# SCH___2023-03-02.net
KiCad netlist of a schematic drawn in EasyEDA
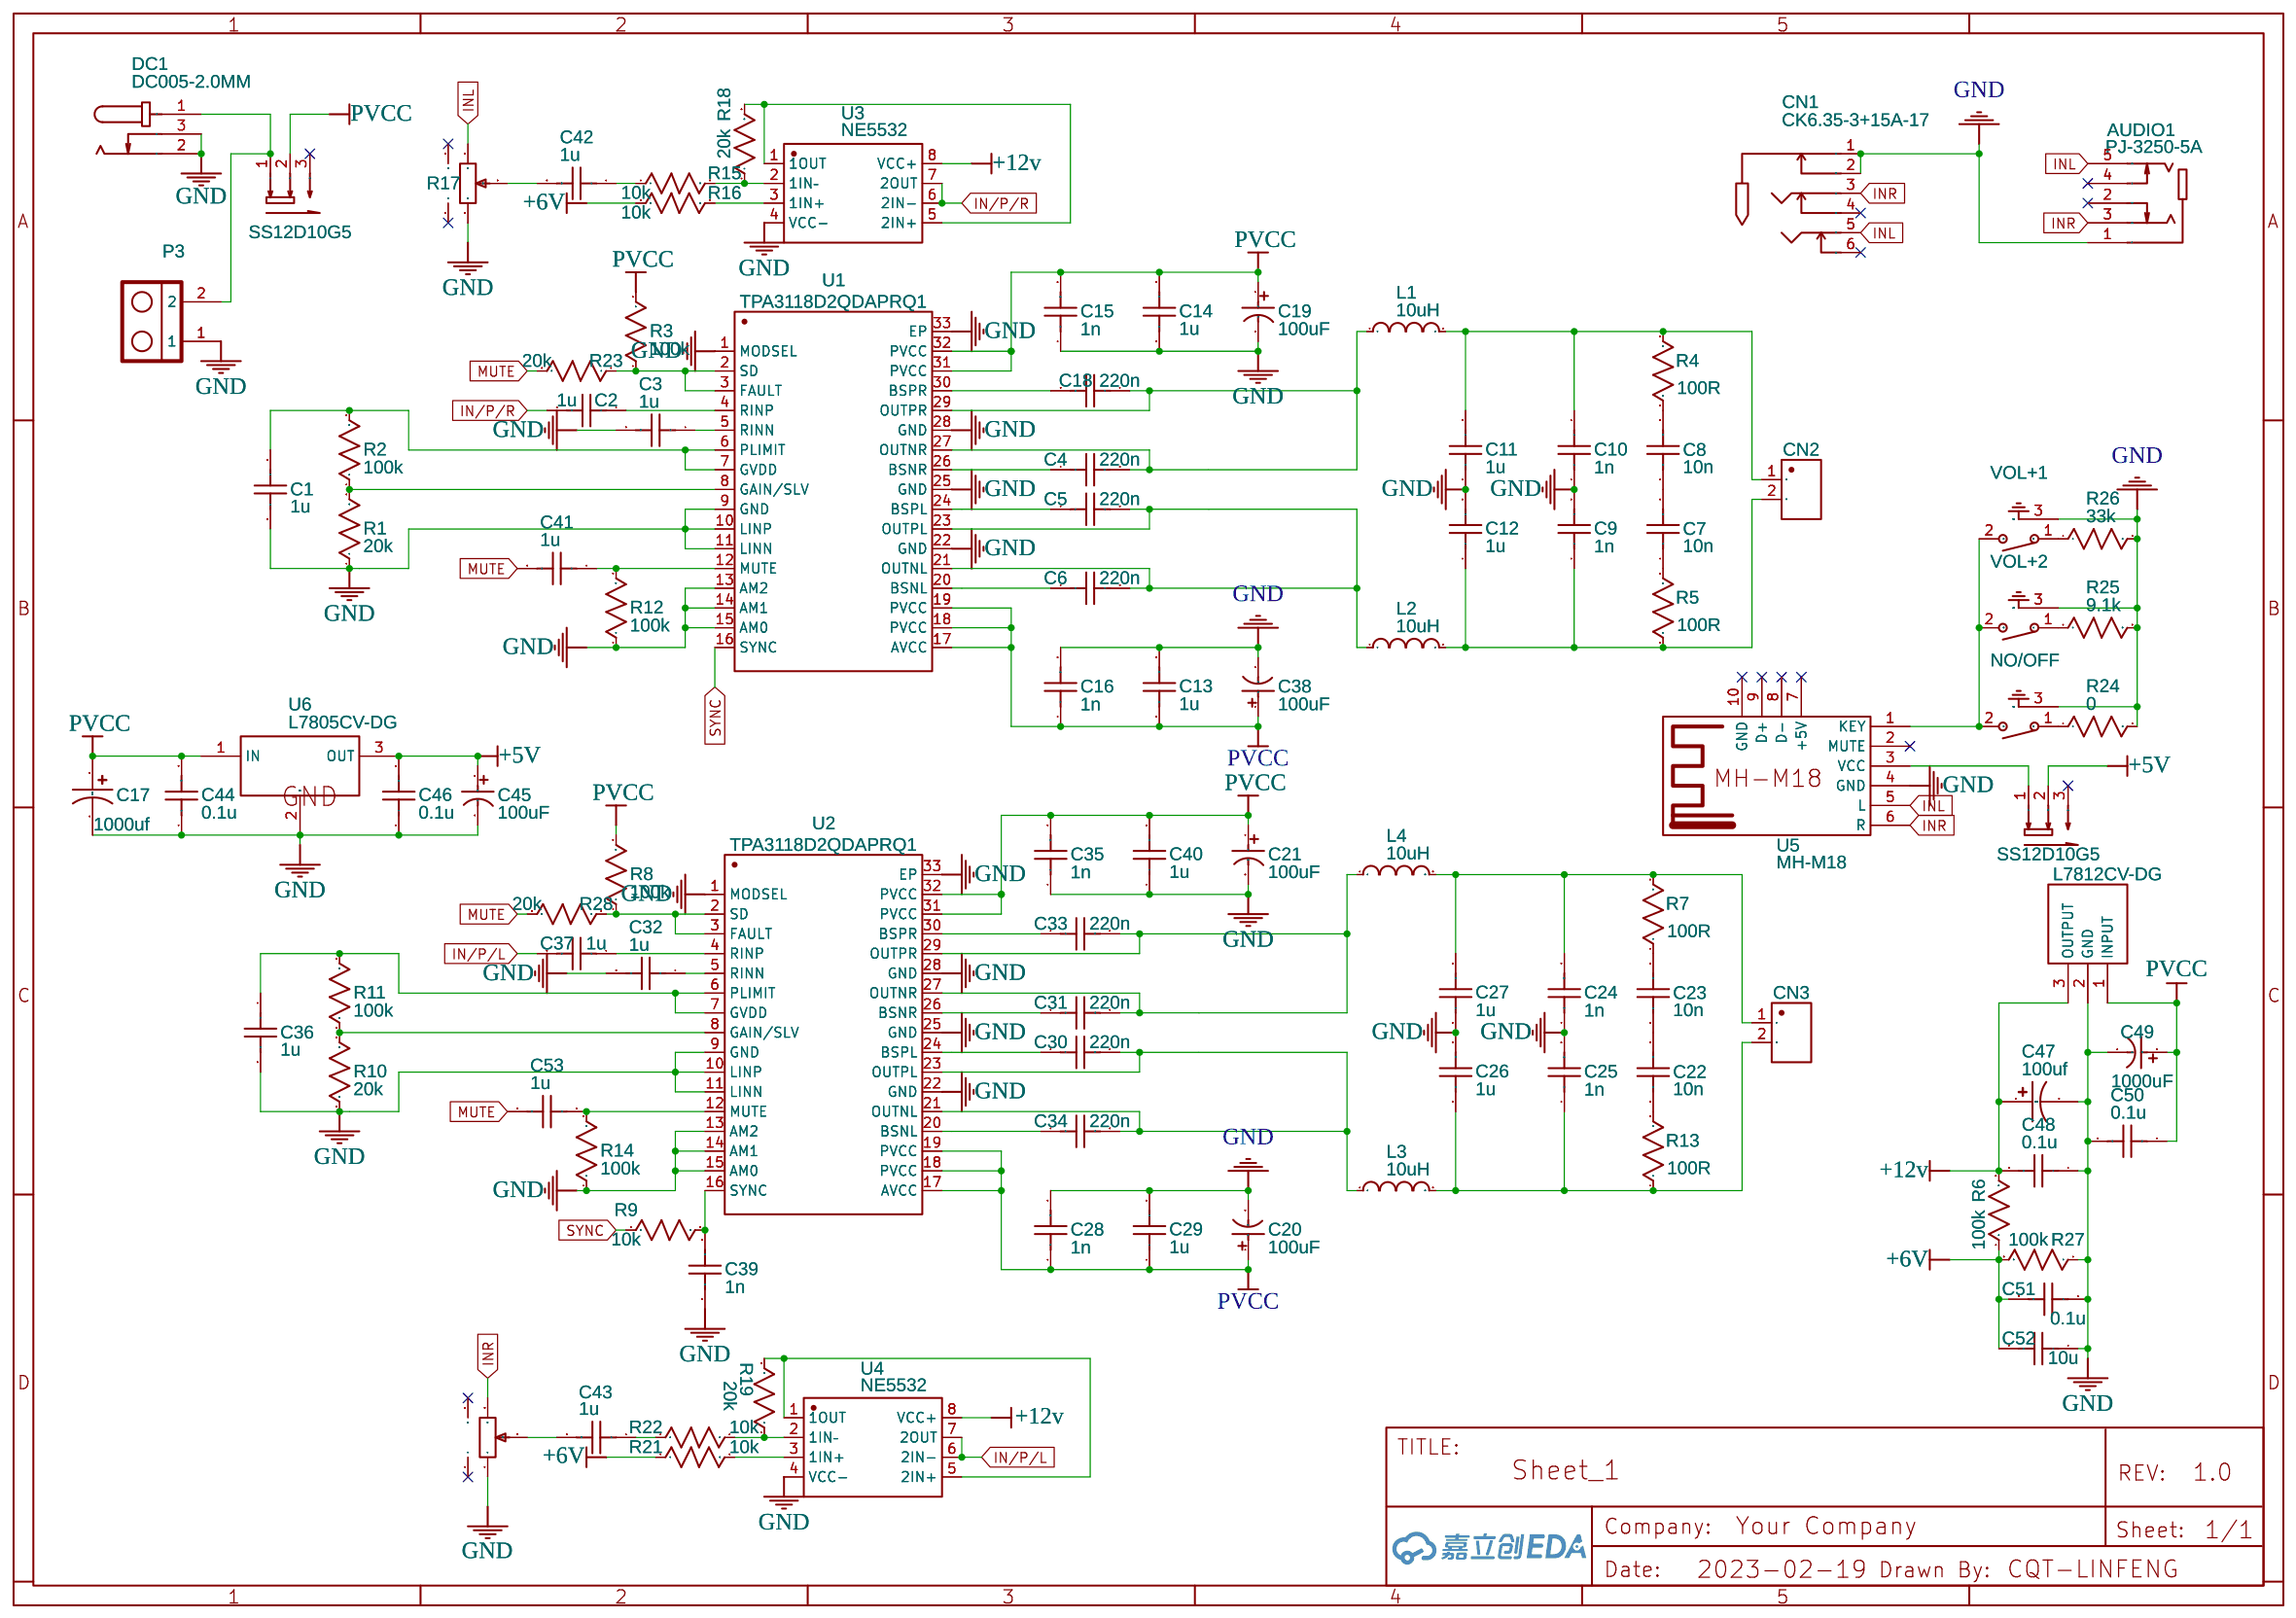
[diagram p0: schematic sheet]

(export (version "E")
  (design (tool "Eeschema 10.0.6"))
  (components
    (comp (ref "AUDIO1")
      (value "PJ-3250-5A")
      (fields (field (name "BOM_Supplier Part") "C165947"))
      (libsource (lib "") (part "PJ-3250-5A"))
    )
    (comp (ref "C1") (value "1u") (libsource (lib "") (part "C_0402_US_3")))
    (comp (ref "C2") (value "1u") (libsource (lib "") (part "C_0402_US_1")))
    (comp (ref "C3") (value "1u") (libsource (lib "") (part "C_0402_US_1")))
    (comp (ref "C4") (value "220n") (libsource (lib "") (part "C_0402_US")))
    (comp (ref "C5") (value "220n") (libsource (lib "") (part "C_0402_US")))
    (comp (ref "C6") (value "220n") (libsource (lib "") (part "C_0402_US")))
    (comp (ref "C7") (value "10n") (libsource (lib "") (part "C_0402_US_2")))
    (comp (ref "C8") (value "10n") (libsource (lib "") (part "C_0402_US_2")))
    (comp (ref "C9") (value "1n") (libsource (lib "") (part "C_0402_US_2")))
    (comp (ref "C10") (value "1n") (libsource (lib "") (part "C_0402_US_2")))
    (comp (ref "C11") (value "1u") (libsource (lib "") (part "C_0402_US_2")))
    (comp (ref "C12") (value "1u") (libsource (lib "") (part "C_0402_US_2")))
    (comp (ref "C13") (value "1u") (libsource (lib "") (part "C_0402_US_2")))
    (comp (ref "C14") (value "1u") (libsource (lib "") (part "C_0402_US_2")))
    (comp (ref "C15") (value "1n") (libsource (lib "") (part "C_0402_US_2")))
    (comp (ref "C16") (value "1n") (libsource (lib "") (part "C_0402_US_2")))
    (comp (ref "C17") (value "1000uf") (libsource (lib "") (part "CE_SMD_D6.3×H5.5_US_1")))
    (comp (ref "C18") (value "220n") (libsource (lib "") (part "C_0603_US")))
    (comp (ref "C19")
      (value "100uF")
      (fields
        (field (name "BOM_Manufacturer Part") "35ZLH100MEFC6.3X11")
        (field (name "BOM_Supplier Part") "C109392")
      )
      (libsource (lib "") (part "35ZLH100MEFC6.3X11_1"))
    )
    (comp (ref "C20")
      (value "100uF")
      (fields
        (field (name "BOM_Manufacturer Part") "35ZLH100MEFC6.3X11")
        (field (name "BOM_Supplier Part") "C109392")
      )
      (libsource (lib "") (part "35ZLH100MEFC6.3X11"))
    )
    (comp (ref "C21")
      (value "100uF")
      (fields
        (field (name "BOM_Manufacturer Part") "35ZLH100MEFC6.3X11")
        (field (name "BOM_Supplier Part") "C109392")
      )
      (libsource (lib "") (part "35ZLH100MEFC6.3X11_1"))
    )
    (comp (ref "C22") (value "10n") (libsource (lib "") (part "C_0402_US_2")))
    (comp (ref "C23") (value "10n") (libsource (lib "") (part "C_0402_US_2")))
    (comp (ref "C24") (value "1n") (libsource (lib "") (part "C_0402_US_2")))
    (comp (ref "C25") (value "1n") (libsource (lib "") (part "C_0402_US_2")))
    (comp (ref "C26") (value "1u") (libsource (lib "") (part "C_0402_US_2")))
    (comp (ref "C27") (value "1u") (libsource (lib "") (part "C_0402_US_2")))
    (comp (ref "C28") (value "1n") (libsource (lib "") (part "C_0402_US_2")))
    (comp (ref "C29") (value "1u") (libsource (lib "") (part "C_0402_US_2")))
    (comp (ref "C30") (value "220n") (libsource (lib "") (part "C_0402_US")))
    (comp (ref "C31") (value "220n") (libsource (lib "") (part "C_0402_US")))
    (comp (ref "C32") (value "1u") (libsource (lib "") (part "C_0402_US_1")))
    (comp (ref "C33") (value "220n") (libsource (lib "") (part "C_0402_US")))
    (comp (ref "C34") (value "220n") (libsource (lib "") (part "C_0402_US")))
    (comp (ref "C35") (value "1n") (libsource (lib "") (part "C_0402_US_2")))
    (comp (ref "C36") (value "1u") (libsource (lib "") (part "C_0402_US_3")))
    (comp (ref "C37") (value "1u") (libsource (lib "") (part "C_0402_US_1")))
    (comp (ref "C38")
      (value "100uF")
      (fields
        (field (name "BOM_Manufacturer Part") "35ZLH100MEFC6.3X11")
        (field (name "BOM_Supplier Part") "C109392")
      )
      (libsource (lib "") (part "35ZLH100MEFC6.3X11"))
    )
    (comp (ref "C39") (value "1n") (libsource (lib "") (part "C_0402_US_2")))
    (comp (ref "C40") (value "1u") (libsource (lib "") (part "C_0402_US_2")))
    (comp (ref "C41") (value "1u") (libsource (lib "") (part "C_0402_US_1")))
    (comp (ref "C42") (value "1u") (libsource (lib "") (part "C_0402_US_1")))
    (comp (ref "C43") (value "1u") (libsource (lib "") (part "C_0402_US_1")))
    (comp (ref "C44") (value "0.1u") (libsource (lib "") (part "C_0402_US_2")))
    (comp (ref "C45")
      (value "100uF")
      (fields
        (field (name "BOM_Manufacturer Part") "35ZLH100MEFC6.3X11")
        (field (name "BOM_Supplier Part") "C109392")
      )
      (libsource (lib "") (part "35ZLH100MEFC6.3X11_1"))
    )
    (comp (ref "C46") (value "0.1u") (libsource (lib "") (part "C_0402_US_2")))
    (comp (ref "C47") (value "100uf") (libsource (lib "") (part "CE_SMD_D6.3×H5.5_US")))
    (comp (ref "C48") (value "0.1u") (libsource (lib "") (part "C_0402_US_1")))
    (comp (ref "C49")
      (value "1000uF")
      (fields
        (field (name "BOM_Manufacturer Part") "35ZLH100MEFC6.3X11")
        (field (name "BOM_Supplier Part") "C109392")
      )
      (libsource (lib "") (part "35ZLH100MEFC6.3X11_2"))
    )
    (comp (ref "C50") (value "0.1u") (libsource (lib "") (part "C_0402_US_1")))
    (comp (ref "C51") (value "0.1u") (libsource (lib "") (part "C_0402_US_1")))
    (comp (ref "C52") (value "10u") (libsource (lib "") (part "C_0402_US_1")))
    (comp (ref "C53") (value "1u") (libsource (lib "") (part "C_0402_US_1")))
    (comp (ref "CN1")
      (value "CK6.35-3+15A-17")
      (fields (field (name "BOM_Supplier Part") "C718061"))
      (libsource (lib "") (part "CK6.35-3+15A-17"))
    )
    (comp (ref "CN2")
      (value "A2002WV-2P")
      (fields (field (name "BOM_Supplier Part") "C273055"))
      (libsource (lib "") (part "A2002WV-2P"))
    )
    (comp (ref "CN3")
      (value "A2002WV-2P")
      (fields (field (name "BOM_Supplier Part") "C273055"))
      (libsource (lib "") (part "A2002WV-2P"))
    )
    (comp (ref "DC1")
      (value "DC005-2.0MM")
      (fields (field (name "BOM_Supplier Part") "C111567"))
      (libsource (lib "") (part "DC005-2.0MM"))
    )
    (comp (ref "L1")
      (value "10uH")
      (fields
        (field (name "BOM_Manufacturer Part") "SMDRH104R-100MT")
        (field (name "BOM_Supplier Part") "C9935")
      )
      (libsource (lib "") (part "SMDRH104R-100MT"))
    )
    (comp (ref "L2")
      (value "10uH")
      (fields
        (field (name "BOM_Manufacturer Part") "SMDRH104R-100MT")
        (field (name "BOM_Supplier Part") "C9935")
      )
      (libsource (lib "") (part "SMDRH104R-100MT"))
    )
    (comp (ref "L3")
      (value "10uH")
      (fields
        (field (name "BOM_Manufacturer Part") "SMDRH104R-100MT")
        (field (name "BOM_Supplier Part") "C9935")
      )
      (libsource (lib "") (part "SMDRH104R-100MT"))
    )
    (comp (ref "L4")
      (value "10uH")
      (fields
        (field (name "BOM_Manufacturer Part") "SMDRH104R-100MT")
        (field (name "BOM_Supplier Part") "C9935")
      )
      (libsource (lib "") (part "SMDRH104R-100MT"))
    )
    (comp (ref "NO/OFF") (value "侧按键") (libsource (lib "") (part "侧按键")))
    (comp (ref "P3")
      (value "端子2P KF128_2  5.08端子-2   PCB端子")
      (fields (field (name "BOM_Manufacturer Part") "接线端子2P"))
      (libsource (lib "") (part "端子2P KF128_2  5.08端子-2   PCB端子"))
    )
    (comp (ref "R1") (value "20k") (libsource (lib "") (part "R_0402_US")))
    (comp (ref "R2") (value "100k") (libsource (lib "") (part "R_0402_US")))
    (comp (ref "R3") (value "100k") (libsource (lib "") (part "R_0402_US")))
    (comp (ref "R4") (value "100R") (libsource (lib "") (part "R_0402_US")))
    (comp (ref "R5") (value "100R") (libsource (lib "") (part "R_0402_US")))
    (comp (ref "R6") (value "100k") (libsource (lib "") (part "R_0603_US_1")))
    (comp (ref "R7") (value "100R") (libsource (lib "") (part "R_0402_US")))
    (comp (ref "R8") (value "100k") (libsource (lib "") (part "R_0402_US")))
    (comp (ref "R9") (value "10k") (libsource (lib "") (part "R_0402_US_1")))
    (comp (ref "R10") (value "20k") (libsource (lib "") (part "R_0402_US")))
    (comp (ref "R11") (value "100k") (libsource (lib "") (part "R_0402_US")))
    (comp (ref "R12") (value "100k") (libsource (lib "") (part "R_0402_US")))
    (comp (ref "R13") (value "100R") (libsource (lib "") (part "R_0402_US")))
    (comp (ref "R14") (value "100k") (libsource (lib "") (part "R_0402_US")))
    (comp (ref "R15") (value "10k") (libsource (lib "") (part "R_0402_US_1")))
    (comp (ref "R16") (value "10k") (libsource (lib "") (part "R_0402_US_1")))
    (comp (ref "R17")
      (value "RV09AF-40-15K-B10K-0C")
      (fields (field (name "BOM_Supplier Part") "C5151446"))
      (libsource (lib "") (part "RV09AF-40-15K-B10K-0C"))
    )
    (comp (ref "R18") (value "20k") (libsource (lib "") (part "R_0402_US")))
    (comp (ref "R19") (value "20k") (libsource (lib "") (part "R_0402_US")))
    (comp (ref "R20")
      (value "RV09AF-40-15K-B10K-0C")
      (fields (field (name "BOM_Supplier Part") "C5151446"))
      (libsource (lib "") (part "RV09AF-40-15K-B10K-0C"))
    )
    (comp (ref "R21") (value "10k") (libsource (lib "") (part "R_0402_US_1")))
    (comp (ref "R22") (value "10k") (libsource (lib "") (part "R_0402_US_1")))
    (comp (ref "R23") (value "20k") (libsource (lib "") (part "R_0402_US_2")))
    (comp (ref "R24") (value "0") (libsource (lib "") (part "R_0402_US_1")))
    (comp (ref "R25") (value "9.1k") (libsource (lib "") (part "R_0402_US_1")))
    (comp (ref "R26") (value "33k") (libsource (lib "") (part "R_0402_US_1")))
    (comp (ref "R27") (value "100k") (libsource (lib "") (part "R_0603_US")))
    (comp (ref "R28") (value "20k") (libsource (lib "") (part "R_0402_US_2")))
    (comp (ref "SW1") (value "SS12D10G5") (libsource (lib "") (part "SS12D10G5")))
    (comp (ref "SW2") (value "SS12D10G5") (libsource (lib "") (part "SS12D10G5")))
    (comp (ref "U1")
      (value "TPA3118D2QDAPRQ1")
      (fields (field (name "BOM_Supplier Part") "C2863787"))
      (libsource (lib "") (part "TPA3118D2QDAPRQ1"))
    )
    (comp (ref "U2")
      (value "TPA3118D2QDAPRQ1")
      (fields (field (name "BOM_Supplier Part") "C2863787"))
      (libsource (lib "") (part "TPA3118D2QDAPRQ1"))
    )
    (comp (ref "U3")
      (value "NE5532")
      (fields (field (name "BOM_Supplier Part") "C9900016784"))
      (libsource (lib "") (part "NE5532"))
    )
    (comp (ref "U4")
      (value "NE5532")
      (fields (field (name "BOM_Supplier Part") "C9900016784"))
      (libsource (lib "") (part "NE5532"))
    )
    (comp (ref "U5") (value "MH-M18") (libsource (lib "") (part "MH-M18")))
    (comp (ref "U6")
      (value "L7805CV-DG")
      (fields (field (name "BOM_Supplier Part") "C3795"))
      (libsource (lib "") (part "L7805CV-DG"))
    )
    (comp (ref "U7")
      (value "L7812CV-DG")
      (fields (field (name "BOM_Supplier Part") "C2914"))
      (libsource (lib "") (part "L7812CV-DG"))
    )
    (comp (ref "VOL+1") (value "侧按键") (libsource (lib "") (part "侧按键_1")))
    (comp (ref "VOL+2") (value "侧按键") (libsource (lib "") (part "侧按键_1")))
  )
  (nets
    (net (code "1") (name "+5V") (class "Default")
      (node (ref "C45") (pin "1") (pinfunction "1_1") (pintype "input"))
      (node (ref "C46") (pin "2") (pinfunction "2_2") (pintype "unspecified"))
      (node (ref "SW1") (pin "2") (pinfunction "2_2") (pintype "unspecified"))
      (node (ref "U6") (pin "3") (pinfunction "OUT_3") (pintype "passive"))
    )
    (net (code "2") (name "+6V") (class "Default")
      (node (ref "C51") (pin "2") (pinfunction "2_2") (pintype "unspecified"))
      (node (ref "C52") (pin "2") (pinfunction "2_2") (pintype "unspecified"))
      (node (ref "R16") (pin "1") (pinfunction "1_1") (pintype "unspecified"))
      (node (ref "R21") (pin "1") (pinfunction "1_1") (pintype "unspecified"))
      (node (ref "R27") (pin "2") (pinfunction "2_2") (pintype "unspecified"))
      (node (ref "R6") (pin "1") (pinfunction "1_1") (pintype "unspecified"))
    )
    (net (code "3") (name "+12v") (class "Default")
      (node (ref "C47") (pin "1") (pinfunction "1_1") (pintype "unspecified"))
      (node (ref "C48") (pin "2") (pinfunction "2_2") (pintype "unspecified"))
      (node (ref "R6") (pin "2") (pinfunction "2_2") (pintype "unspecified"))
      (node (ref "U3") (pin "8") (pinfunction "VCC+_8") (pintype "unspecified"))
      (node (ref "U4") (pin "8") (pinfunction "VCC+_8") (pintype "unspecified"))
      (node (ref "U7") (pin "3") (pinfunction "OUTPUT_3") (pintype "unspecified"))
    )
    (net (code "4") (name "GND") (class "Default")
      (node (ref "AUDIO1") (pin "1") (pinfunction "1_1") (pintype "unspecified"))
      (node (ref "C1") (pin "2") (pinfunction "2_2") (pintype "unspecified"))
      (node (ref "C10") (pin "1") (pinfunction "1_1") (pintype "unspecified"))
      (node (ref "C11") (pin "1") (pinfunction "1_1") (pintype "unspecified"))
      (node (ref "C12") (pin "2") (pinfunction "2_2") (pintype "unspecified"))
      (node (ref "C13") (pin "2") (pinfunction "2_2") (pintype "unspecified"))
      (node (ref "C14") (pin "1") (pinfunction "1_1") (pintype "unspecified"))
      (node (ref "C15") (pin "1") (pinfunction "1_1") (pintype "unspecified"))
      (node (ref "C16") (pin "2") (pinfunction "2_2") (pintype "unspecified"))
      (node (ref "C17") (pin "2") (pinfunction "2_2") (pintype "unspecified"))
      (node (ref "C19") (pin "2") (pinfunction "2_2") (pintype "input"))
      (node (ref "C20") (pin "2") (pinfunction "2_2") (pintype "input"))
      (node (ref "C21") (pin "2") (pinfunction "2_2") (pintype "input"))
      (node (ref "C24") (pin "1") (pinfunction "1_1") (pintype "unspecified"))
      (node (ref "C25") (pin "2") (pinfunction "2_2") (pintype "unspecified"))
      (node (ref "C26") (pin "2") (pinfunction "2_2") (pintype "unspecified"))
      (node (ref "C27") (pin "1") (pinfunction "1_1") (pintype "unspecified"))
      (node (ref "C28") (pin "2") (pinfunction "2_2") (pintype "unspecified"))
      (node (ref "C29") (pin "2") (pinfunction "2_2") (pintype "unspecified"))
      (node (ref "C3") (pin "2") (pinfunction "2_2") (pintype "unspecified"))
      (node (ref "C32") (pin "2") (pinfunction "2_2") (pintype "unspecified"))
      (node (ref "C35") (pin "1") (pinfunction "1_1") (pintype "unspecified"))
      (node (ref "C36") (pin "2") (pinfunction "2_2") (pintype "unspecified"))
      (node (ref "C38") (pin "2") (pinfunction "2_2") (pintype "input"))
      (node (ref "C39") (pin "1") (pinfunction "1_1") (pintype "unspecified"))
      (node (ref "C40") (pin "1") (pinfunction "1_1") (pintype "unspecified"))
      (node (ref "C44") (pin "1") (pinfunction "1_1") (pintype "unspecified"))
      (node (ref "C45") (pin "2") (pinfunction "2_2") (pintype "input"))
      (node (ref "C46") (pin "1") (pinfunction "1_1") (pintype "unspecified"))
      (node (ref "C47") (pin "2") (pinfunction "2_2") (pintype "unspecified"))
      (node (ref "C48") (pin "1") (pinfunction "1_1") (pintype "unspecified"))
      (node (ref "C49") (pin "2") (pinfunction "2_2") (pintype "input"))
      (node (ref "C50") (pin "2") (pinfunction "2_2") (pintype "unspecified"))
      (node (ref "C51") (pin "1") (pinfunction "1_1") (pintype "unspecified"))
      (node (ref "C52") (pin "1") (pinfunction "1_1") (pintype "unspecified"))
      (node (ref "C9") (pin "2") (pinfunction "2_2") (pintype "unspecified"))
      (node (ref "CN1") (pin "1") (pinfunction "1_1") (pintype "input"))
      (node (ref "CN1") (pin "2") (pinfunction "2_2") (pintype "input"))
      (node (ref "DC1") (pin "2") (pinfunction "2_2") (pintype "unspecified"))
      (node (ref "DC1") (pin "3") (pinfunction "3_3") (pintype "unspecified"))
      (node (ref "NO/OFF") (pin "3") (pinfunction "GND_3") (pintype "unspecified"))
      (node (ref "P3") (pin "1") (pinfunction "1_1") (pintype "unspecified"))
      (node (ref "R1") (pin "1") (pinfunction "1_1") (pintype "unspecified"))
      (node (ref "R10") (pin "1") (pinfunction "1_1") (pintype "unspecified"))
      (node (ref "R12") (pin "1") (pinfunction "1_1") (pintype "unspecified"))
      (node (ref "R14") (pin "1") (pinfunction "1_1") (pintype "unspecified"))
      (node (ref "R17") (pin "1") (pinfunction "1_1") (pintype "input"))
      (node (ref "R20") (pin "1") (pinfunction "1_1") (pintype "input"))
      (node (ref "R24") (pin "2") (pinfunction "2_2") (pintype "unspecified"))
      (node (ref "R25") (pin "2") (pinfunction "2_2") (pintype "unspecified"))
      (node (ref "R26") (pin "2") (pinfunction "2_2") (pintype "unspecified"))
      (node (ref "R27") (pin "1") (pinfunction "1_1") (pintype "unspecified"))
      (node (ref "U1") (pin "1") (pinfunction "MODSEL_1") (pintype "unspecified"))
      (node (ref "U1") (pin "10") (pinfunction "LINP_10") (pintype "unspecified"))
      (node (ref "U1") (pin "11") (pinfunction "LINN_11") (pintype "unspecified"))
      (node (ref "U1") (pin "13") (pinfunction "AM2_13") (pintype "unspecified"))
      (node (ref "U1") (pin "14") (pinfunction "AM1_14") (pintype "unspecified"))
      (node (ref "U1") (pin "15") (pinfunction "AM0_15") (pintype "unspecified"))
      (node (ref "U1") (pin "22") (pinfunction "GND_22") (pintype "unspecified"))
      (node (ref "U1") (pin "25") (pinfunction "GND_25") (pintype "unspecified"))
      (node (ref "U1") (pin "28") (pinfunction "GND_28") (pintype "unspecified"))
      (node (ref "U1") (pin "33") (pinfunction "EP_33") (pintype "unspecified"))
      (node (ref "U1") (pin "9") (pinfunction "GND_9") (pintype "unspecified"))
      (node (ref "U2") (pin "1") (pinfunction "MODSEL_1") (pintype "unspecified"))
      (node (ref "U2") (pin "10") (pinfunction "LINP_10") (pintype "unspecified"))
      (node (ref "U2") (pin "11") (pinfunction "LINN_11") (pintype "unspecified"))
      (node (ref "U2") (pin "13") (pinfunction "AM2_13") (pintype "unspecified"))
      (node (ref "U2") (pin "14") (pinfunction "AM1_14") (pintype "unspecified"))
      (node (ref "U2") (pin "15") (pinfunction "AM0_15") (pintype "unspecified"))
      (node (ref "U2") (pin "22") (pinfunction "GND_22") (pintype "unspecified"))
      (node (ref "U2") (pin "25") (pinfunction "GND_25") (pintype "unspecified"))
      (node (ref "U2") (pin "28") (pinfunction "GND_28") (pintype "unspecified"))
      (node (ref "U2") (pin "33") (pinfunction "EP_33") (pintype "unspecified"))
      (node (ref "U2") (pin "9") (pinfunction "GND_9") (pintype "unspecified"))
      (node (ref "U3") (pin "4") (pinfunction "VCC-_4") (pintype "unspecified"))
      (node (ref "U4") (pin "4") (pinfunction "VCC-_4") (pintype "unspecified"))
      (node (ref "U5") (pin "4") (pinfunction "GND_4") (pintype "unspecified"))
      (node (ref "U6") (pin "2") (pinfunction "GND_2") (pintype "passive"))
      (node (ref "U7") (pin "2") (pinfunction "GND_2") (pintype "unspecified"))
      (node (ref "VOL+1") (pin "3") (pinfunction "GND_3") (pintype "unspecified"))
      (node (ref "VOL+2") (pin "3") (pinfunction "GND_3") (pintype "unspecified"))
    )
    (net (code "5") (name "INL") (class "Default")
      (node (ref "AUDIO1") (pin "5") (pinfunction "5_5") (pintype "unspecified"))
      (node (ref "CN1") (pin "5") (pinfunction "5_5") (pintype "input"))
      (node (ref "R17") (pin "3") (pinfunction "3_3") (pintype "input"))
      (node (ref "U5") (pin "5") (pinfunction "L_5") (pintype "unspecified"))
    )
    (net (code "6") (name "INR") (class "Default")
      (node (ref "AUDIO1") (pin "3") (pinfunction "3_3") (pintype "unspecified"))
      (node (ref "CN1") (pin "3") (pinfunction "3_3") (pintype "input"))
      (node (ref "R20") (pin "3") (pinfunction "3_3") (pintype "input"))
      (node (ref "U5") (pin "6") (pinfunction "R_6") (pintype "unspecified"))
    )
    (net (code "7") (name "IN{slash}P{slash}L") (class "Default")
      (node (ref "C37") (pin "2") (pinfunction "2_2") (pintype "unspecified"))
      (node (ref "U4") (pin "6") (pinfunction "2IN-_6") (pintype "unspecified"))
      (node (ref "U4") (pin "7") (pinfunction "2OUT_7") (pintype "unspecified"))
    )
    (net (code "8") (name "IN{slash}P{slash}R") (class "Default")
      (node (ref "C2") (pin "2") (pinfunction "2_2") (pintype "unspecified"))
      (node (ref "U3") (pin "6") (pinfunction "2IN-_6") (pintype "unspecified"))
      (node (ref "U3") (pin "7") (pinfunction "2OUT_7") (pintype "unspecified"))
    )
    (net (code "9") (name "MUTE") (class "Default")
      (node (ref "C41") (pin "2") (pinfunction "2_2") (pintype "unspecified"))
      (node (ref "C53") (pin "2") (pinfunction "2_2") (pintype "unspecified"))
      (node (ref "R23") (pin "2") (pinfunction "2_2") (pintype "unspecified"))
      (node (ref "R28") (pin "2") (pinfunction "2_2") (pintype "unspecified"))
    )
    (net (code "10") (name "Net-(C7-Pad1)") (class "Default")
      (node (ref "C7") (pin "1") (pinfunction "1_1") (pintype "unspecified"))
      (node (ref "R5") (pin "2") (pinfunction "2_2") (pintype "unspecified"))
    )
    (net (code "11") (name "Net-(C7-Pad2)") (class "Default")
      (node (ref "C7") (pin "2") (pinfunction "2_2") (pintype "unspecified"))
      (node (ref "C8") (pin "1") (pinfunction "1_1") (pintype "unspecified"))
    )
    (net (code "12") (name "Net-(C8-Pad2)") (class "Default")
      (node (ref "C8") (pin "2") (pinfunction "2_2") (pintype "unspecified"))
      (node (ref "R4") (pin "1") (pinfunction "1_1") (pintype "unspecified"))
    )
    (net (code "13") (name "Net-(C10-Pad2)") (class "Default")
      (node (ref "C10") (pin "2") (pinfunction "2_2") (pintype "unspecified"))
      (node (ref "C11") (pin "2") (pinfunction "2_2") (pintype "unspecified"))
      (node (ref "CN2") (pin "1") (pinfunction "1_1") (pintype "unspecified"))
      (node (ref "L1") (pin "2") (pinfunction "2_2") (pintype "unspecified"))
      (node (ref "R4") (pin "2") (pinfunction "2_2") (pintype "unspecified"))
    )
    (net (code "14") (name "Net-(C12-Pad1)") (class "Default")
      (node (ref "C12") (pin "1") (pinfunction "1_1") (pintype "unspecified"))
      (node (ref "C9") (pin "1") (pinfunction "1_1") (pintype "unspecified"))
      (node (ref "CN2") (pin "2") (pinfunction "2_2") (pintype "unspecified"))
      (node (ref "L2") (pin "2") (pinfunction "2_2") (pintype "unspecified"))
      (node (ref "R5") (pin "1") (pinfunction "1_1") (pintype "unspecified"))
    )
    (net (code "15") (name "Net-(C22-Pad1)") (class "Default")
      (node (ref "C22") (pin "1") (pinfunction "1_1") (pintype "unspecified"))
      (node (ref "R13") (pin "2") (pinfunction "2_2") (pintype "unspecified"))
    )
    (net (code "16") (name "Net-(C22-Pad2)") (class "Default")
      (node (ref "C22") (pin "2") (pinfunction "2_2") (pintype "unspecified"))
      (node (ref "C23") (pin "1") (pinfunction "1_1") (pintype "unspecified"))
    )
    (net (code "17") (name "Net-(C23-Pad2)") (class "Default")
      (node (ref "C23") (pin "2") (pinfunction "2_2") (pintype "unspecified"))
      (node (ref "R7") (pin "1") (pinfunction "1_1") (pintype "unspecified"))
    )
    (net (code "18") (name "Net-(C24-Pad2)") (class "Default")
      (node (ref "C24") (pin "2") (pinfunction "2_2") (pintype "unspecified"))
      (node (ref "C27") (pin "2") (pinfunction "2_2") (pintype "unspecified"))
      (node (ref "CN3") (pin "1") (pinfunction "1_1") (pintype "unspecified"))
      (node (ref "L4") (pin "2") (pinfunction "2_2") (pintype "unspecified"))
      (node (ref "R7") (pin "2") (pinfunction "2_2") (pintype "unspecified"))
    )
    (net (code "19") (name "Net-(C25-Pad1)") (class "Default")
      (node (ref "C25") (pin "1") (pinfunction "1_1") (pintype "unspecified"))
      (node (ref "C26") (pin "1") (pinfunction "1_1") (pintype "unspecified"))
      (node (ref "CN3") (pin "2") (pinfunction "2_2") (pintype "unspecified"))
      (node (ref "L3") (pin "2") (pinfunction "2_2") (pintype "unspecified"))
      (node (ref "R13") (pin "1") (pinfunction "1_1") (pintype "unspecified"))
    )
    (net (code "20") (name "Net-(C42-Pad1)") (class "Default")
      (node (ref "C42") (pin "1") (pinfunction "1_1") (pintype "unspecified"))
      (node (ref "R15") (pin "1") (pinfunction "1_1") (pintype "unspecified"))
    )
    (net (code "21") (name "Net-(C42-Pad2)") (class "Default")
      (node (ref "C42") (pin "2") (pinfunction "2_2") (pintype "unspecified"))
      (node (ref "R17") (pin "2") (pinfunction "2_2") (pintype "input"))
    )
    (net (code "22") (name "Net-(C43-Pad1)") (class "Default")
      (node (ref "C43") (pin "1") (pinfunction "1_1") (pintype "unspecified"))
      (node (ref "R22") (pin "1") (pinfunction "1_1") (pintype "unspecified"))
    )
    (net (code "23") (name "Net-(C43-Pad2)") (class "Default")
      (node (ref "C43") (pin "2") (pinfunction "2_2") (pintype "unspecified"))
      (node (ref "R20") (pin "2") (pinfunction "2_2") (pintype "input"))
    )
    (net (code "24") (name "Net-(DC1-Pad1)") (class "Default")
      (node (ref "DC1") (pin "1") (pinfunction "1_1") (pintype "unspecified"))
      (node (ref "P3") (pin "2") (pinfunction "2_2") (pintype "unspecified"))
      (node (ref "SW2") (pin "1") (pinfunction "1_1") (pintype "unspecified"))
    )
    (net (code "25") (name "Net-(NO/OFF-Pad1)") (class "Default")
      (node (ref "NO/OFF") (pin "1") (pinfunction "1_1") (pintype "unspecified"))
      (node (ref "R24") (pin "1") (pinfunction "1_1") (pintype "unspecified"))
    )
    (net (code "26") (name "Net-(R25-Pad1)") (class "Default")
      (node (ref "R25") (pin "1") (pinfunction "1_1") (pintype "unspecified"))
      (node (ref "VOL+2") (pin "1") (pinfunction "1_1") (pintype "unspecified"))
    )
    (net (code "27") (name "Net-(R26-Pad1)") (class "Default")
      (node (ref "R26") (pin "1") (pinfunction "1_1") (pintype "unspecified"))
      (node (ref "VOL+1") (pin "1") (pinfunction "1_1") (pintype "unspecified"))
    )
    (net (code "28") (name "Net-(U1-BSNL)") (class "Default")
      (node (ref "C6") (pin "1") (pinfunction "1_1") (pintype "unspecified"))
      (node (ref "U1") (pin "20") (pinfunction "BSNL_20") (pintype "unspecified"))
    )
    (net (code "29") (name "Net-(U1-BSNR)") (class "Default")
      (node (ref "C4") (pin "1") (pinfunction "1_1") (pintype "unspecified"))
      (node (ref "U1") (pin "26") (pinfunction "BSNR_26") (pintype "unspecified"))
    )
    (net (code "30") (name "Net-(U1-BSPL)") (class "Default")
      (node (ref "C5") (pin "1") (pinfunction "1_1") (pintype "unspecified"))
      (node (ref "U1") (pin "24") (pinfunction "BSPL_24") (pintype "unspecified"))
    )
    (net (code "31") (name "Net-(U1-BSPR)") (class "Default")
      (node (ref "C18") (pin "2") (pinfunction "2_2") (pintype "unspecified"))
      (node (ref "U1") (pin "30") (pinfunction "BSPR_30") (pintype "unspecified"))
    )
    (net (code "32") (name "Net-(U1-FAULT)") (class "Default")
      (node (ref "R23") (pin "1") (pinfunction "1_1") (pintype "unspecified"))
      (node (ref "R3") (pin "1") (pinfunction "1_1") (pintype "unspecified"))
      (node (ref "U1") (pin "2") (pinfunction "SD_2") (pintype "unspecified"))
      (node (ref "U1") (pin "3") (pinfunction "FAULT_3") (pintype "unspecified"))
    )
    (net (code "33") (name "Net-(U1-GAIN{slash}SLV)") (class "Default")
      (node (ref "R1") (pin "2") (pinfunction "2_2") (pintype "unspecified"))
      (node (ref "R2") (pin "1") (pinfunction "1_1") (pintype "unspecified"))
      (node (ref "U1") (pin "8") (pinfunction "GAIN/SLV_8") (pintype "unspecified"))
    )
    (net (code "34") (name "Net-(U1-GVDD)") (class "Default")
      (node (ref "C1") (pin "1") (pinfunction "1_1") (pintype "unspecified"))
      (node (ref "R2") (pin "2") (pinfunction "2_2") (pintype "unspecified"))
      (node (ref "U1") (pin "6") (pinfunction "PLIMIT_6") (pintype "unspecified"))
      (node (ref "U1") (pin "7") (pinfunction "GVDD_7") (pintype "unspecified"))
    )
    (net (code "35") (name "Net-(U1-MUTE)") (class "Default")
      (node (ref "C41") (pin "1") (pinfunction "1_1") (pintype "unspecified"))
      (node (ref "R12") (pin "2") (pinfunction "2_2") (pintype "unspecified"))
      (node (ref "U1") (pin "12") (pinfunction "MUTE_12") (pintype "unspecified"))
    )
    (net (code "36") (name "Net-(U1-OUTNL)") (class "Default")
      (node (ref "C5") (pin "2") (pinfunction "2_2") (pintype "unspecified"))
      (node (ref "C6") (pin "2") (pinfunction "2_2") (pintype "unspecified"))
      (node (ref "L2") (pin "1") (pinfunction "1_1") (pintype "unspecified"))
      (node (ref "U1") (pin "21") (pinfunction "OUTNL_21") (pintype "unspecified"))
      (node (ref "U1") (pin "23") (pinfunction "OUTPL_23") (pintype "unspecified"))
    )
    (net (code "37") (name "Net-(U1-OUTNR)") (class "Default")
      (node (ref "C18") (pin "1") (pinfunction "1_1") (pintype "unspecified"))
      (node (ref "C4") (pin "2") (pinfunction "2_2") (pintype "unspecified"))
      (node (ref "L1") (pin "1") (pinfunction "1_1") (pintype "unspecified"))
      (node (ref "U1") (pin "27") (pinfunction "OUTNR_27") (pintype "unspecified"))
      (node (ref "U1") (pin "29") (pinfunction "OUTPR_29") (pintype "unspecified"))
    )
    (net (code "38") (name "Net-(U1-RINN)") (class "Default")
      (node (ref "C3") (pin "1") (pinfunction "1_1") (pintype "unspecified"))
      (node (ref "U1") (pin "5") (pinfunction "RINN_5") (pintype "unspecified"))
    )
    (net (code "39") (name "Net-(U1-RINP)") (class "Default")
      (node (ref "C2") (pin "1") (pinfunction "1_1") (pintype "unspecified"))
      (node (ref "U1") (pin "4") (pinfunction "RINP_4") (pintype "unspecified"))
    )
    (net (code "40") (name "Net-(U2-BSNL)") (class "Default")
      (node (ref "C34") (pin "1") (pinfunction "1_1") (pintype "unspecified"))
      (node (ref "U2") (pin "20") (pinfunction "BSNL_20") (pintype "unspecified"))
    )
    (net (code "41") (name "Net-(U2-BSNR)") (class "Default")
      (node (ref "C31") (pin "1") (pinfunction "1_1") (pintype "unspecified"))
      (node (ref "U2") (pin "26") (pinfunction "BSNR_26") (pintype "unspecified"))
    )
    (net (code "42") (name "Net-(U2-BSPL)") (class "Default")
      (node (ref "C30") (pin "1") (pinfunction "1_1") (pintype "unspecified"))
      (node (ref "U2") (pin "24") (pinfunction "BSPL_24") (pintype "unspecified"))
    )
    (net (code "43") (name "Net-(U2-BSPR)") (class "Default")
      (node (ref "C33") (pin "1") (pinfunction "1_1") (pintype "unspecified"))
      (node (ref "U2") (pin "30") (pinfunction "BSPR_30") (pintype "unspecified"))
    )
    (net (code "44") (name "Net-(U2-FAULT)") (class "Default")
      (node (ref "R28") (pin "1") (pinfunction "1_1") (pintype "unspecified"))
      (node (ref "R8") (pin "1") (pinfunction "1_1") (pintype "unspecified"))
      (node (ref "U2") (pin "2") (pinfunction "SD_2") (pintype "unspecified"))
      (node (ref "U2") (pin "3") (pinfunction "FAULT_3") (pintype "unspecified"))
    )
    (net (code "45") (name "Net-(U2-GAIN{slash}SLV)") (class "Default")
      (node (ref "R10") (pin "2") (pinfunction "2_2") (pintype "unspecified"))
      (node (ref "R11") (pin "1") (pinfunction "1_1") (pintype "unspecified"))
      (node (ref "U2") (pin "8") (pinfunction "GAIN/SLV_8") (pintype "unspecified"))
    )
    (net (code "46") (name "Net-(U2-GVDD)") (class "Default")
      (node (ref "C36") (pin "1") (pinfunction "1_1") (pintype "unspecified"))
      (node (ref "R11") (pin "2") (pinfunction "2_2") (pintype "unspecified"))
      (node (ref "U2") (pin "6") (pinfunction "PLIMIT_6") (pintype "unspecified"))
      (node (ref "U2") (pin "7") (pinfunction "GVDD_7") (pintype "unspecified"))
    )
    (net (code "47") (name "Net-(U2-MUTE)") (class "Default")
      (node (ref "C53") (pin "1") (pinfunction "1_1") (pintype "unspecified"))
      (node (ref "R14") (pin "2") (pinfunction "2_2") (pintype "unspecified"))
      (node (ref "U2") (pin "12") (pinfunction "MUTE_12") (pintype "unspecified"))
    )
    (net (code "48") (name "Net-(U2-OUTNL)") (class "Default")
      (node (ref "C30") (pin "2") (pinfunction "2_2") (pintype "unspecified"))
      (node (ref "C34") (pin "2") (pinfunction "2_2") (pintype "unspecified"))
      (node (ref "L3") (pin "1") (pinfunction "1_1") (pintype "unspecified"))
      (node (ref "U2") (pin "21") (pinfunction "OUTNL_21") (pintype "unspecified"))
      (node (ref "U2") (pin "23") (pinfunction "OUTPL_23") (pintype "unspecified"))
    )
    (net (code "49") (name "Net-(U2-OUTNR)") (class "Default")
      (node (ref "C31") (pin "2") (pinfunction "2_2") (pintype "unspecified"))
      (node (ref "C33") (pin "2") (pinfunction "2_2") (pintype "unspecified"))
      (node (ref "L4") (pin "1") (pinfunction "1_1") (pintype "unspecified"))
      (node (ref "U2") (pin "27") (pinfunction "OUTNR_27") (pintype "unspecified"))
      (node (ref "U2") (pin "29") (pinfunction "OUTPR_29") (pintype "unspecified"))
    )
    (net (code "50") (name "Net-(U2-RINN)") (class "Default")
      (node (ref "C32") (pin "1") (pinfunction "1_1") (pintype "unspecified"))
      (node (ref "U2") (pin "5") (pinfunction "RINN_5") (pintype "unspecified"))
    )
    (net (code "51") (name "Net-(U2-RINP)") (class "Default")
      (node (ref "C37") (pin "1") (pinfunction "1_1") (pintype "unspecified"))
      (node (ref "U2") (pin "4") (pinfunction "RINP_4") (pintype "unspecified"))
    )
    (net (code "52") (name "Net-(U2-SYNC)") (class "Default")
      (node (ref "C39") (pin "2") (pinfunction "2_2") (pintype "unspecified"))
      (node (ref "R9") (pin "2") (pinfunction "2_2") (pintype "unspecified"))
      (node (ref "U2") (pin "16") (pinfunction "SYNC_16") (pintype "unspecified"))
    )
    (net (code "53") (name "Net-(U3-1IN+)") (class "Default")
      (node (ref "R16") (pin "2") (pinfunction "2_2") (pintype "unspecified"))
      (node (ref "U3") (pin "3") (pinfunction "1IN+_3") (pintype "unspecified"))
    )
    (net (code "54") (name "Net-(U3-1IN–)") (class "Default")
      (node (ref "R15") (pin "2") (pinfunction "2_2") (pintype "unspecified"))
      (node (ref "R18") (pin "1") (pinfunction "1_1") (pintype "unspecified"))
      (node (ref "U3") (pin "2") (pinfunction "1IN–_2") (pintype "unspecified"))
    )
    (net (code "55") (name "Net-(U3-1OUT)") (class "Default")
      (node (ref "R18") (pin "2") (pinfunction "2_2") (pintype "unspecified"))
      (node (ref "U3") (pin "1") (pinfunction "1OUT_1") (pintype "unspecified"))
      (node (ref "U3") (pin "5") (pinfunction "2IN+_5") (pintype "unspecified"))
    )
    (net (code "56") (name "Net-(U4-1IN+)") (class "Default")
      (node (ref "R21") (pin "2") (pinfunction "2_2") (pintype "unspecified"))
      (node (ref "U4") (pin "3") (pinfunction "1IN+_3") (pintype "unspecified"))
    )
    (net (code "57") (name "Net-(U4-1IN–)") (class "Default")
      (node (ref "R19") (pin "1") (pinfunction "1_1") (pintype "unspecified"))
      (node (ref "R22") (pin "2") (pinfunction "2_2") (pintype "unspecified"))
      (node (ref "U4") (pin "2") (pinfunction "1IN–_2") (pintype "unspecified"))
    )
    (net (code "58") (name "Net-(U4-1OUT)") (class "Default")
      (node (ref "R19") (pin "2") (pinfunction "2_2") (pintype "unspecified"))
      (node (ref "U4") (pin "1") (pinfunction "1OUT_1") (pintype "unspecified"))
      (node (ref "U4") (pin "5") (pinfunction "2IN+_5") (pintype "unspecified"))
    )
    (net (code "59") (name "Net-(U5-KEY)") (class "Default")
      (node (ref "NO/OFF") (pin "2") (pinfunction "2_2") (pintype "unspecified"))
      (node (ref "U5") (pin "1") (pinfunction "KEY_1") (pintype "unspecified"))
      (node (ref "VOL+1") (pin "2") (pinfunction "2_2") (pintype "unspecified"))
      (node (ref "VOL+2") (pin "2") (pinfunction "2_2") (pintype "unspecified"))
    )
    (net (code "60") (name "Net-(U5-VCC)") (class "Default")
      (node (ref "SW1") (pin "1") (pinfunction "1_1") (pintype "unspecified"))
      (node (ref "U5") (pin "3") (pinfunction "VCC_3") (pintype "unspecified"))
    )
    (net (code "61") (name "PVCC") (class "Default")
      (node (ref "C13") (pin "1") (pinfunction "1_1") (pintype "unspecified"))
      (node (ref "C14") (pin "2") (pinfunction "2_2") (pintype "unspecified"))
      (node (ref "C15") (pin "2") (pinfunction "2_2") (pintype "unspecified"))
      (node (ref "C16") (pin "1") (pinfunction "1_1") (pintype "unspecified"))
      (node (ref "C17") (pin "1") (pinfunction "1_1") (pintype "unspecified"))
      (node (ref "C19") (pin "1") (pinfunction "1_1") (pintype "input"))
      (node (ref "C20") (pin "1") (pinfunction "1_1") (pintype "input"))
      (node (ref "C21") (pin "1") (pinfunction "1_1") (pintype "input"))
      (node (ref "C28") (pin "1") (pinfunction "1_1") (pintype "unspecified"))
      (node (ref "C29") (pin "1") (pinfunction "1_1") (pintype "unspecified"))
      (node (ref "C35") (pin "2") (pinfunction "2_2") (pintype "unspecified"))
      (node (ref "C38") (pin "1") (pinfunction "1_1") (pintype "input"))
      (node (ref "C40") (pin "2") (pinfunction "2_2") (pintype "unspecified"))
      (node (ref "C44") (pin "2") (pinfunction "2_2") (pintype "unspecified"))
      (node (ref "C49") (pin "1") (pinfunction "1_1") (pintype "input"))
      (node (ref "C50") (pin "1") (pinfunction "1_1") (pintype "unspecified"))
      (node (ref "R3") (pin "2") (pinfunction "2_2") (pintype "unspecified"))
      (node (ref "R8") (pin "2") (pinfunction "2_2") (pintype "unspecified"))
      (node (ref "SW2") (pin "2") (pinfunction "2_2") (pintype "unspecified"))
      (node (ref "U1") (pin "17") (pinfunction "AVCC_17") (pintype "unspecified"))
      (node (ref "U1") (pin "18") (pinfunction "PVCC_18") (pintype "unspecified"))
      (node (ref "U1") (pin "19") (pinfunction "PVCC_19") (pintype "unspecified"))
      (node (ref "U1") (pin "31") (pinfunction "PVCC_31") (pintype "unspecified"))
      (node (ref "U1") (pin "32") (pinfunction "PVCC_32") (pintype "unspecified"))
      (node (ref "U2") (pin "17") (pinfunction "AVCC_17") (pintype "unspecified"))
      (node (ref "U2") (pin "18") (pinfunction "PVCC_18") (pintype "unspecified"))
      (node (ref "U2") (pin "19") (pinfunction "PVCC_19") (pintype "unspecified"))
      (node (ref "U2") (pin "31") (pinfunction "PVCC_31") (pintype "unspecified"))
      (node (ref "U2") (pin "32") (pinfunction "PVCC_32") (pintype "unspecified"))
      (node (ref "U6") (pin "1") (pinfunction "IN_1") (pintype "passive"))
      (node (ref "U7") (pin "1") (pinfunction "INPUT_1") (pintype "unspecified"))
    )
    (net (code "62") (name "SYNC") (class "Default")
      (node (ref "R9") (pin "1") (pinfunction "1_1") (pintype "unspecified"))
      (node (ref "U1") (pin "16") (pinfunction "SYNC_16") (pintype "unspecified"))
    )
    (net (code "63") (name "unconnected-(AUDIO1-Pad2)") (class "Default")
      (node (ref "AUDIO1") (pin "2") (pinfunction "2_2") (pintype "unspecified+no_connect"))
    )
    (net (code "64") (name "unconnected-(AUDIO1-Pad4)") (class "Default")
      (node (ref "AUDIO1") (pin "4") (pinfunction "4_4") (pintype "unspecified+no_connect"))
    )
    (net (code "65") (name "unconnected-(CN1-Pad4)") (class "Default")
      (node (ref "CN1") (pin "4") (pinfunction "4_4") (pintype "input+no_connect"))
    )
    (net (code "66") (name "unconnected-(CN1-Pad6)") (class "Default")
      (node (ref "CN1") (pin "6") (pinfunction "6_6") (pintype "input+no_connect"))
    )
    (net (code "67") (name "unconnected-(R17-Pad4)") (class "Default")
      (node (ref "R17") (pin "4") (pinfunction "4_4") (pintype "input+no_connect"))
    )
    (net (code "68") (name "unconnected-(R17-Pad5)") (class "Default")
      (node (ref "R17") (pin "5") (pinfunction "5_5") (pintype "input+no_connect"))
    )
    (net (code "69") (name "unconnected-(R20-Pad4)") (class "Default")
      (node (ref "R20") (pin "4") (pinfunction "4_4") (pintype "input+no_connect"))
    )
    (net (code "70") (name "unconnected-(R20-Pad5)") (class "Default")
      (node (ref "R20") (pin "5") (pinfunction "5_5") (pintype "input+no_connect"))
    )
    (net (code "71") (name "unconnected-(SW1-Pad3)") (class "Default")
      (node (ref "SW1") (pin "3") (pinfunction "3_3") (pintype "unspecified+no_connect"))
    )
    (net (code "72") (name "unconnected-(SW2-Pad3)") (class "Default")
      (node (ref "SW2") (pin "3") (pinfunction "3_3") (pintype "unspecified+no_connect"))
    )
    (net (code "73") (name "unconnected-(U5-+5V-Pad7)") (class "Default")
      (node (ref "U5") (pin "7") (pinfunction "+5V_7") (pintype "unspecified+no_connect"))
    )
    (net (code "74") (name "unconnected-(U5-D+-Pad9)") (class "Default")
      (node (ref "U5") (pin "9") (pinfunction "D+_9") (pintype "unspecified+no_connect"))
    )
    (net (code "75") (name "unconnected-(U5-D--Pad8)") (class "Default")
      (node (ref "U5") (pin "8") (pinfunction "D-_8") (pintype "unspecified+no_connect"))
    )
    (net (code "76") (name "unconnected-(U5-GND-Pad10)") (class "Default")
      (node (ref "U5") (pin "10") (pinfunction "GND_10") (pintype "unspecified+no_connect"))
    )
    (net (code "77") (name "unconnected-(U5-MUTE-Pad2)") (class "Default")
      (node (ref "U5") (pin "2") (pinfunction "MUTE_2") (pintype "unspecified+no_connect"))
    )
  )
)
